# Power_supply_UCM_updated.net
KiCad netlist of a schematic drawn in Altium Designer
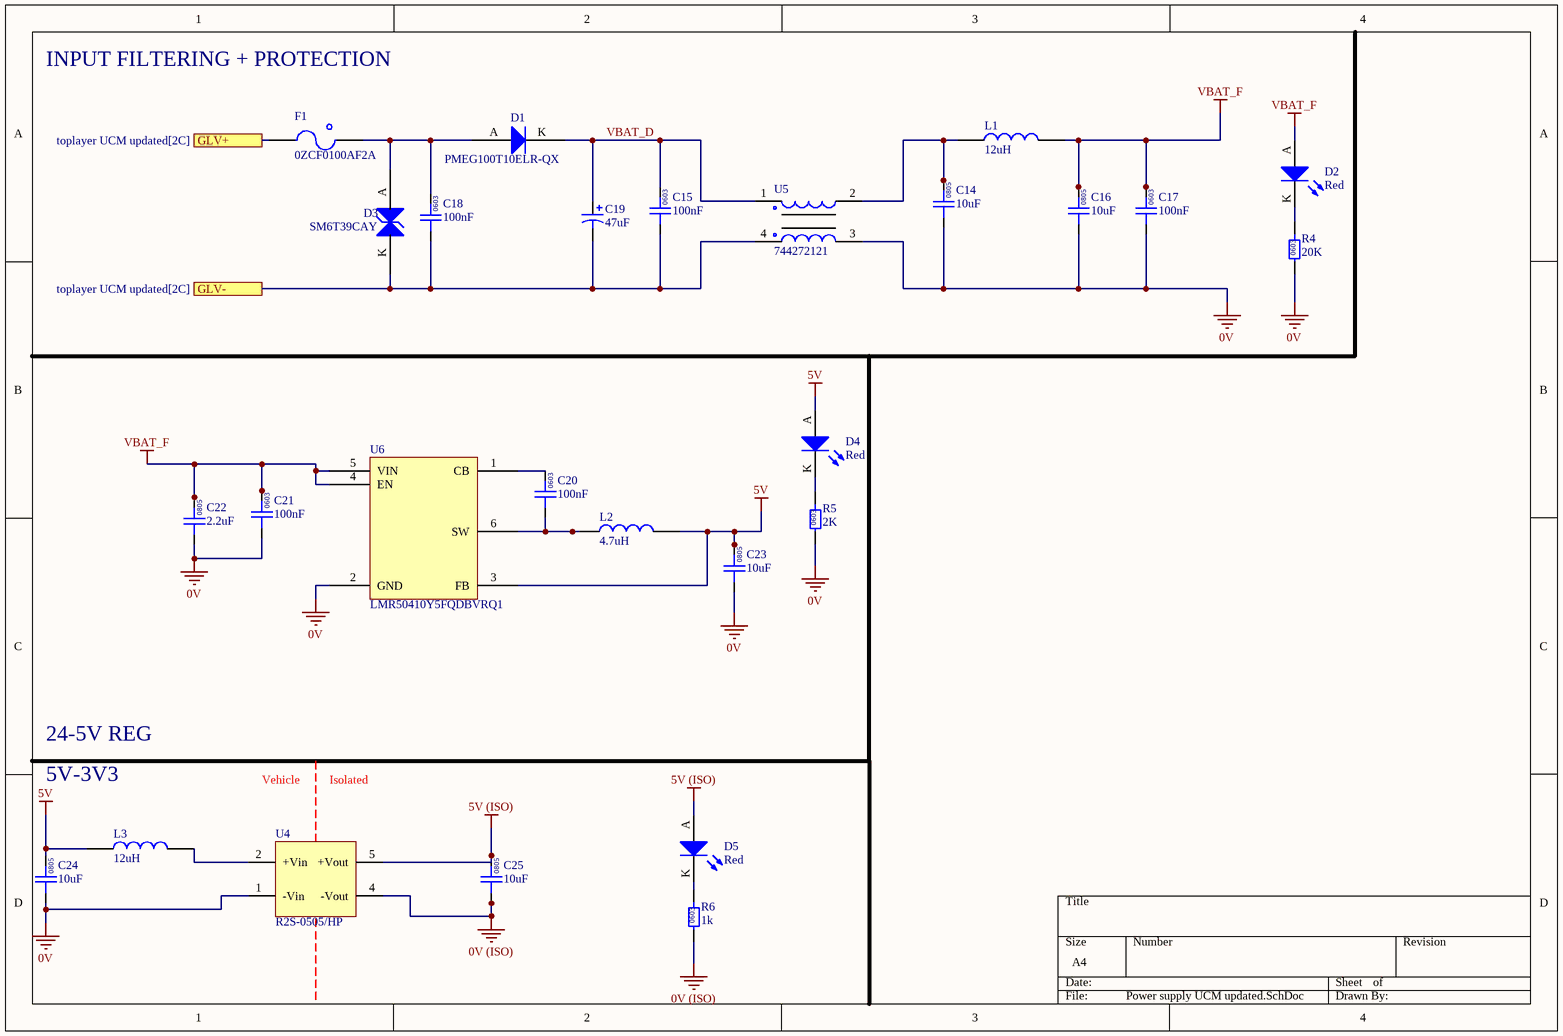
[diagram p0: Power supply UCM updated.SchDoc]

(export (version "E")
  (design (tool "Eeschema 10.0.6"))
  (components
    (comp (ref "C14")
      (value "10uF")
      (footprint "0805")
      (fields
        (field (name "PART NUMBER") "GRM21BR6YA106KE43L")
        (field (name "MANUFACTURER") "muRata")
        (field (name "TOLERANCE") "10%")
      )
      (libsource (lib "ts_standard_library") (part "Capacitor 0805"))
    )
    (comp (ref "C15")
      (value "100nF")
      (footprint "0603")
      (fields
        (field (name "PART NUMBER") "GCM188L81H104KA57D")
        (field (name "MANUFACTURER") "muRata")
        (field (name "TOLERANCE") "±10%")
      )
      (libsource (lib "ts_standard_library") (part "Capacitor 0603"))
    )
    (comp (ref "C16")
      (value "10uF")
      (footprint "0805")
      (fields
        (field (name "PART NUMBER") "GRM21BR6YA106KE43L")
        (field (name "MANUFACTURER") "muRata")
        (field (name "TOLERANCE") "10%")
      )
      (libsource (lib "ts_standard_library") (part "Capacitor 0805"))
    )
    (comp (ref "C17")
      (value "100nF")
      (footprint "0603")
      (fields
        (field (name "PART NUMBER") "GCM188L81H104KA57D")
        (field (name "MANUFACTURER") "muRata")
        (field (name "TOLERANCE") "±10%")
      )
      (libsource (lib "ts_standard_library") (part "Capacitor 0603"))
    )
    (comp (ref "C18")
      (value "100nF")
      (footprint "0603")
      (fields
        (field (name "PART NUMBER") "GCM188L81H104KA57D")
        (field (name "MANUFACTURER") "muRata")
        (field (name "TOLERANCE") "±10%")
      )
      (libsource (lib "ts_standard_library") (part "Capacitor 0603"))
    )
    (comp (ref "C19")
      (value "47uF")
      (footprint "CHEMI-CON ELCO")
      (fields (field (name "PART NUMBER") "HHXA350ARA470MF61G"))
      (libsource (lib "ts_standard_library") (part "Capacitor (Polarised)"))
    )
    (comp (ref "C20")
      (value "100nF")
      (footprint "0603")
      (fields
        (field (name "PART NUMBER") "GCM188L81H104KA57D")
        (field (name "MANUFACTURER") "muRata")
        (field (name "TOLERANCE") "±10%")
      )
      (libsource (lib "ts_standard_library") (part "Capacitor 0603"))
    )
    (comp (ref "C21")
      (value "100nF")
      (footprint "0603")
      (fields
        (field (name "PART NUMBER") "GCM188L81H104KA57D")
        (field (name "MANUFACTURER") "muRata")
        (field (name "TOLERANCE") "±10%")
      )
      (libsource (lib "ts_standard_library") (part "Capacitor 0603"))
    )
    (comp (ref "C22")
      (value "2.2uF")
      (footprint "0805")
      (fields
        (field (name "PART NUMBER") "GRM21BR61A226ME51L")
        (field (name "MANUFACTURER") "muRata")
        (field (name "TOLERANCE") "20%")
      )
      (libsource (lib "ts_standard_library") (part "Capacitor 0805"))
    )
    (comp (ref "C23")
      (value "10uF")
      (footprint "0805")
      (fields
        (field (name "PART NUMBER") "GRM21BR6YA106KE43L")
        (field (name "MANUFACTURER") "muRata")
        (field (name "TOLERANCE") "10%")
      )
      (libsource (lib "ts_standard_library") (part "Capacitor 0805"))
    )
    (comp (ref "C24")
      (value "10uF")
      (footprint "0805")
      (fields
        (field (name "PART NUMBER") "GRM21BR6YA106KE43L")
        (field (name "MANUFACTURER") "muRata")
        (field (name "TOLERANCE") "10%")
      )
      (libsource (lib "ts_standard_library") (part "Capacitor 0805"))
    )
    (comp (ref "C25")
      (value "10uF")
      (footprint "0805")
      (fields
        (field (name "PART NUMBER") "GRM21BR6YA106KE43L")
        (field (name "MANUFACTURER") "muRata")
        (field (name "TOLERANCE") "10%")
      )
      (libsource (lib "ts_standard_library") (part "Capacitor 0805"))
    )
    (comp (ref "D1")
      (value "PMEG100T10ELR-QX")
      (footprint "SODFL350X110-2N")
      (description "Diode 100 V 1A Surface Mount SOD-123W")
      (libsource (lib "Team Swinburne") (part "PMEG100T10ELR-QX"))
    )
    (comp (ref "D2")
      (value "Red")
      (footprint "0805 LED")
      (description "Red LED Indication - Discrete 1.75V 0805 (2012 Metric)")
      (fields (field (name "PART NUMBER") "SML-210LTT86") (field (name "MANUFACTURER") "ROHM Semiconductor"))
      (libsource (lib "ts_standard_library") (part "LED"))
    )
    (comp (ref "D3")
      (value "SM6T39CAY")
      (footprint "SM6T39CAY-Footprint-1")
      (description "TVS Diode Single Bi-Dir 33.3V 600W Automotive 2-Pin SMB T/R / TVS DIODE 33.3VWM 69.7VC SMB")
      (libsource (lib "Team Swinburne") (part "SM6T39CAY-Symbol"))
    )
    (comp (ref "D4")
      (value "Red")
      (footprint "0805 LED")
      (description "Red LED Indication - Discrete 1.75V 0805 (2012 Metric)")
      (fields (field (name "PART NUMBER") "SML-210LTT86") (field (name "MANUFACTURER") "ROHM Semiconductor"))
      (libsource (lib "ts_standard_library") (part "LED"))
    )
    (comp (ref "D5")
      (value "Red")
      (footprint "0805 LED")
      (description "Red LED Indication - Discrete 1.75V 0805 (2012 Metric)")
      (fields (field (name "PART NUMBER") "SML-210LTT86") (field (name "MANUFACTURER") "ROHM Semiconductor"))
      (libsource (lib "ts_standard_library") (part "LED"))
    )
    (comp (ref "F1")
      (value "0ZCF0100AF2A")
      (footprint "2920")
      (description "PTC RESET FUSE 60V 1A 292")
      (fields
        (field (name "MANUFACTURER") "Littelfuse Inc.")
        (field (name "DIGIKEY PART NUMBER") "507-2070-1-ND")
      )
      (libsource (lib "ts_standard_library") (part "PTC Fuse"))
    )
    (comp (ref "L1")
      (value "12uH")
      (footprint "1812")
      (fields
        (field (name "PART NUMBER") "RLS-126")
        (field (name "MANUFACTURER") "Recom")
        (field (name "TOLERANCE") "0.2")
      )
      (libsource (lib "ts_standard_library") (part "Inductor"))
    )
    (comp (ref "L2")
      (value "4.7uH")
      (footprint "SRN3015TA-4R7M")
      (fields
        (field (name "PART NUMBER") "SRN4018-4R7M")
        (field (name "MANUFACTURER") "Bourns")
        (field (name "TOLERANCE") "0.2")
      )
      (libsource (lib "ts_standard_library") (part "Inductor"))
    )
    (comp (ref "L3")
      (value "12uH")
      (footprint "1812")
      (fields
        (field (name "PART NUMBER") "RLS-126")
        (field (name "MANUFACTURER") "Recom")
        (field (name "TOLERANCE") "0.2")
      )
      (libsource (lib "ts_standard_library") (part "Inductor"))
    )
    (comp (ref "R4")
      (value "20K")
      (footprint "0603")
      (fields
        (field (name "PART NUMBER") "RC0603FR-0720KL")
        (field (name "MANUFACTURER") "YAGEO")
        (field (name "TOLERANCE") "0.01")
      )
      (libsource (lib "ts_standard_library") (part "Resistor 0603"))
    )
    (comp (ref "R5")
      (value "2K")
      (footprint "0603")
      (fields
        (field (name "PART NUMBER") "RC0603FR-072KL")
        (field (name "MANUFACTURER") "YAGEO")
        (field (name "TOLERANCE") "0.01")
      )
      (libsource (lib "ts_standard_library") (part "Resistor 0603"))
    )
    (comp (ref "R6")
      (value "1k")
      (footprint "0603")
      (fields
        (field (name "PART NUMBER") "RC0603FR-071KL")
        (field (name "MANUFACTURER") "YAGEO")
        (field (name "TOLERANCE") "0.01")
      )
      (libsource (lib "ts_standard_library") (part "Resistor 0603"))
    )
    (comp (ref "U4")
      (value "R2S-0505/HP")
      (footprint "RECOM 8-SMD (5 Pin)")
      (description "Isolated Module DC DC Converter 1 Output 5V 606mA 4.5V - 5.5V Input")
      (fields (field (name "MANUFACTURER") "Recom") (field (name "DIGIKEY PART NUMBER") "945-1764-5-ND"))
      (libsource (lib "ts_20-standard-library") (part "R2S-0505/HP"))
    )
    (comp (ref "U5")
      (value "744272121")
      (footprint "Wurth 4-PC Pad")
      (fields
        (field (name "MANUFACTURER") "Wurth Electronics Inc")
        (field (name "DIGIKEY PART NUMBER") "732-1489-1-ND")
      )
      (libsource (lib "ts_standard_library") (part "CM Choke"))
    )
    (comp (ref "U6")
      (value "LMR50410Y5FQDBVRQ1")
      (footprint "TI-SOT23-6")
      (description "IC REG BUCK 5V 1A SOT23-6")
      (fields (field (name "PART NUMBER") "LMR50410-Q1") (field (name "MANUFACTURER") "Texas Instruments"))
      (libsource (lib "ts_standard_library") (part "LMR50410Y5FQDBVRQ1"))
    )
  )
  (nets
    (net (code "1") (name "/GLV+") (class "Default")
      (node (ref "F1") (pin "1") (pinfunction "1_1") (pintype "passive"))
    )
    (net (code "2") (name "/GLV-") (class "Default")
      (node (ref "C15") (pin "1") (pinfunction "1_1") (pintype "passive"))
      (node (ref "C18") (pin "1") (pinfunction "1_1") (pintype "passive"))
      (node (ref "C19") (pin "1") (pinfunction "1_1") (pintype "passive"))
      (node (ref "D3") (pin "K") (pintype "passive"))
      (node (ref "U5") (pin "4") (pinfunction "4_4") (pintype "passive"))
    )
    (net (code "3") (name "/VBAT_D") (class "Default")
      (node (ref "C15") (pin "2") (pinfunction "2_2") (pintype "passive"))
      (node (ref "C19") (pin "2") (pinfunction "2_2") (pintype "passive"))
      (node (ref "D1") (pin "K") (pintype "passive"))
      (node (ref "U5") (pin "1") (pinfunction "1_1") (pintype "passive"))
    )
    (net (code "4") (name "0V") (class "Default")
      (node (ref "C14") (pin "1") (pinfunction "1_1") (pintype "passive"))
      (node (ref "C16") (pin "1") (pinfunction "1_1") (pintype "passive"))
      (node (ref "C17") (pin "1") (pinfunction "1_1") (pintype "passive"))
      (node (ref "C21") (pin "1") (pinfunction "1_1") (pintype "passive"))
      (node (ref "C22") (pin "1") (pinfunction "1_1") (pintype "passive"))
      (node (ref "C23") (pin "1") (pinfunction "1_1") (pintype "passive"))
      (node (ref "C24") (pin "1") (pinfunction "1_1") (pintype "passive"))
      (node (ref "R4") (pin "1") (pinfunction "1_1") (pintype "passive"))
      (node (ref "R5") (pin "1") (pinfunction "1_1") (pintype "passive"))
      (node (ref "U4") (pin "1") (pinfunction "-Vin_1") (pintype "power_in"))
      (node (ref "U5") (pin "3") (pinfunction "3_3") (pintype "power_in"))
      (node (ref "U6") (pin "2") (pinfunction "GND_2") (pintype "passive"))
    )
    (net (code "5") (name "0V (ISO)") (class "Default")
      (node (ref "C25") (pin "1") (pinfunction "1_1") (pintype "passive"))
      (node (ref "R6") (pin "1") (pinfunction "1_1") (pintype "passive"))
      (node (ref "U4") (pin "4") (pinfunction "-Vout_4") (pintype "power_in"))
    )
    (net (code "6") (name "5V") (class "Default")
      (node (ref "C23") (pin "2") (pinfunction "2_2") (pintype "passive"))
      (node (ref "C24") (pin "2") (pinfunction "2_2") (pintype "passive"))
      (node (ref "D4") (pin "A") (pinfunction "A_A") (pintype "passive"))
      (node (ref "L2") (pin "1") (pinfunction "1_1") (pintype "passive"))
      (node (ref "L3") (pin "2") (pinfunction "2_2") (pintype "passive"))
      (node (ref "U6") (pin "3") (pinfunction "FB_3") (pintype "passive"))
    )
    (net (code "7") (name "5V (ISO)") (class "Default")
      (node (ref "C25") (pin "2") (pinfunction "2_2") (pintype "passive"))
      (node (ref "D5") (pin "A") (pinfunction "A_A") (pintype "passive"))
      (node (ref "U4") (pin "5") (pinfunction "+Vout_5") (pintype "power_in"))
    )
    (net (code "8") (name "Net-(C14-Pad2)") (class "Default")
      (node (ref "C14") (pin "2") (pinfunction "2_2") (pintype "passive"))
      (node (ref "L1") (pin "2") (pinfunction "2_2") (pintype "passive"))
      (node (ref "U5") (pin "2") (pinfunction "2_2") (pintype "passive"))
    )
    (net (code "9") (name "Net-(C18-Pad2)") (class "Default")
      (node (ref "C18") (pin "2") (pinfunction "2_2") (pintype "passive"))
      (node (ref "D1") (pin "A") (pintype "passive"))
      (node (ref "D3") (pin "A") (pintype "passive"))
      (node (ref "F1") (pin "2") (pinfunction "2_2") (pintype "passive"))
    )
    (net (code "10") (name "Net-(D2-PadK)") (class "Default")
      (node (ref "D2") (pin "K") (pinfunction "K_K") (pintype "passive"))
      (node (ref "R4") (pin "2") (pinfunction "2_2") (pintype "passive"))
    )
    (net (code "11") (name "Net-(D4-PadK)") (class "Default")
      (node (ref "D4") (pin "K") (pinfunction "K_K") (pintype "passive"))
      (node (ref "R5") (pin "2") (pinfunction "2_2") (pintype "passive"))
    )
    (net (code "12") (name "Net-(D5-PadK)") (class "Default")
      (node (ref "D5") (pin "K") (pinfunction "K_K") (pintype "passive"))
      (node (ref "R6") (pin "2") (pinfunction "2_2") (pintype "passive"))
    )
    (net (code "13") (name "Net-(U4-+Vin)") (class "Default")
      (node (ref "L3") (pin "1") (pinfunction "1_1") (pintype "passive"))
      (node (ref "U4") (pin "2") (pinfunction "+Vin_2") (pintype "power_in"))
    )
    (net (code "14") (name "Net-(U6-CB)") (class "Default")
      (node (ref "C20") (pin "2") (pinfunction "2_2") (pintype "passive"))
      (node (ref "U6") (pin "1") (pinfunction "CB_1") (pintype "passive"))
    )
    (net (code "15") (name "Net-(U6-SW)") (class "Default")
      (node (ref "C20") (pin "1") (pinfunction "1_1") (pintype "passive"))
      (node (ref "L2") (pin "2") (pinfunction "2_2") (pintype "passive"))
      (node (ref "U6") (pin "6") (pinfunction "SW_6") (pintype "passive"))
    )
    (net (code "16") (name "VBAT_F") (class "Default")
      (node (ref "C16") (pin "2") (pinfunction "2_2") (pintype "passive"))
      (node (ref "C17") (pin "2") (pinfunction "2_2") (pintype "passive"))
      (node (ref "C21") (pin "2") (pinfunction "2_2") (pintype "passive"))
      (node (ref "C22") (pin "2") (pinfunction "2_2") (pintype "passive"))
      (node (ref "D2") (pin "A") (pinfunction "A_A") (pintype "passive"))
      (node (ref "L1") (pin "1") (pinfunction "1_1") (pintype "passive"))
      (node (ref "U6") (pin "4") (pinfunction "EN_4") (pintype "passive"))
      (node (ref "U6") (pin "5") (pinfunction "VIN_5") (pintype "passive"))
    )
  )
)
